# dashbutton_round_v2.net
KiCad netlist of a schematic drawn in EAGLE
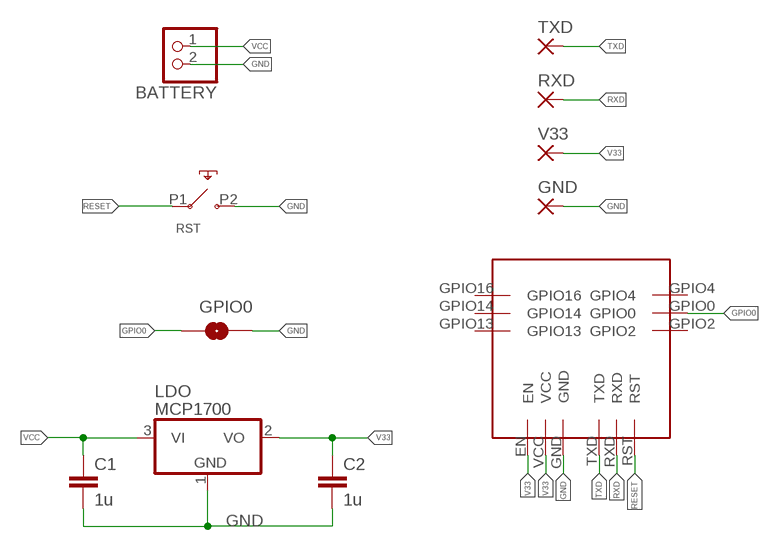
[diagram p0: schematic, sheet 1]

(export (version "E")
  (design (tool "Eeschema 10.0.6"))
  (components
    (comp (ref "BATTERY")
      (value "JST_2PIN-SMT-RA")
      (footprint "eagle-import:JST-PH-2-SMT-RA")
      (libsource (lib "eagle-import") (part "JST_2PIN-SMT-RA"))
    )
    (comp (ref "C1")
      (value "1u")
      (footprint "eagle-import:C1206")
      (libsource (lib "eagle-import") (part "C-EUC1206"))
    )
    (comp (ref "C2")
      (value "1u")
      (footprint "eagle-import:C1206")
      (libsource (lib "eagle-import") (part "C-EUC1206"))
    )
    (comp (ref "GND")
      (value "WIREPADSMD1,27-254")
      (footprint "eagle-import:SMD1,27-2,54")
      (libsource (lib "eagle-import") (part "WIREPADSMD1,27-254"))
    )
    (comp (ref "GPIO0")
      (value "JUMPER-SMT_2_NO_NO-SILK")
      (footprint "eagle-import:SMT-JUMPER_2_NO_NO-SILK")
      (libsource (lib "eagle-import") (part "JUMPER-SMT_2_NO_NO-SILK"))
    )
    (comp (ref "LDO")
      (value "MCP1700")
      (footprint "eagle-import:SOT23")
      (libsource (lib "eagle-import") (part "MCP1703CB"))
    )
    (comp (ref "RST")
      (value "6X3_SMD_BUTTON_HALF")
      (footprint "eagle-import:6X3BUTTON")
      (libsource (lib "eagle-import") (part "6X3_SMD_BUTTON_HALF"))
    )
    (comp (ref "RXD")
      (value "WIREPADSMD1,27-254")
      (footprint "eagle-import:SMD1,27-2,54")
      (libsource (lib "eagle-import") (part "WIREPADSMD1,27-254"))
    )
    (comp (ref "TXD")
      (value "WIREPADSMD1,27-254")
      (footprint "eagle-import:SMD1,27-2,54")
      (libsource (lib "eagle-import") (part "WIREPADSMD1,27-254"))
    )
    (comp (ref "U$1")
      (value "ESP8285-M3")
      (footprint "eagle-import:ESP8285")
      (libsource (lib "eagle-import") (part "ESP8285-M3"))
    )
    (comp (ref "V33")
      (value "WIREPADSMD1,27-254")
      (footprint "eagle-import:SMD1,27-2,54")
      (libsource (lib "eagle-import") (part "WIREPADSMD1,27-254"))
    )
  )
  (nets
    (net (code "1") (name "GND") (class "Default")
      (node (ref "BATTERY") (pin "2") (pinfunction "1_2") (pintype "passive"))
      (node (ref "C1") (pin "2") (pinfunction "2_2") (pintype "passive"))
      (node (ref "C2") (pin "2") (pinfunction "2_2") (pintype "passive"))
      (node (ref "GND") (pin "1") (pinfunction "P_1") (pintype "passive"))
      (node (ref "GPIO0") (pin "2") (pinfunction "2_2") (pintype "passive"))
      (node (ref "LDO") (pin "1") (pinfunction "GND_1") (pintype "passive"))
      (node (ref "RST") (pin "P2") (pinfunction "P2_P2") (pintype "bidirectional"))
      (node (ref "U$1") (pin "GND") (pinfunction "GND_GND") (pintype "bidirectional"))
    )
    (net (code "2") (name "GPIO0") (class "Default")
      (node (ref "GPIO0") (pin "1") (pinfunction "1_1") (pintype "passive"))
      (node (ref "U$1") (pin "GPIO0") (pinfunction "GPIO0_GPIO0") (pintype "bidirectional"))
    )
    (net (code "3") (name "RESET") (class "Default")
      (node (ref "RST") (pin "P1") (pinfunction "P1_P1") (pintype "bidirectional"))
      (node (ref "U$1") (pin "RST") (pinfunction "RST_RST") (pintype "bidirectional"))
    )
    (net (code "4") (name "RXD") (class "Default")
      (node (ref "RXD") (pin "1") (pinfunction "P_1") (pintype "passive"))
      (node (ref "U$1") (pin "RXD") (pinfunction "RXD_RXD") (pintype "bidirectional"))
    )
    (net (code "5") (name "TXD") (class "Default")
      (node (ref "TXD") (pin "1") (pinfunction "P_1") (pintype "passive"))
      (node (ref "U$1") (pin "TXD") (pinfunction "TXD_TXD") (pintype "bidirectional"))
    )
    (net (code "6") (name "V33") (class "Default")
      (node (ref "C2") (pin "1") (pinfunction "1_1") (pintype "passive"))
      (node (ref "LDO") (pin "2") (pinfunction "VO_2") (pintype "passive"))
      (node (ref "U$1") (pin "EN") (pinfunction "EN_EN") (pintype "bidirectional"))
      (node (ref "U$1") (pin "VCC") (pinfunction "VCC_VCC") (pintype "bidirectional"))
      (node (ref "V33") (pin "1") (pinfunction "P_1") (pintype "passive"))
    )
    (net (code "7") (name "VCC") (class "Default")
      (node (ref "BATTERY") (pin "1") (pinfunction "2_1") (pintype "passive"))
      (node (ref "C1") (pin "1") (pinfunction "1_1") (pintype "passive"))
      (node (ref "LDO") (pin "3") (pinfunction "VI_3") (pintype "input"))
    )
    (net (code "8") (name "unconnected-(U$1-PadGPIO2)") (class "Default")
      (node (ref "U$1") (pin "GPIO2") (pinfunction "GPIO2_GPIO2") (pintype "bidirectional"))
    )
    (net (code "9") (name "unconnected-(U$1-PadGPIO4)") (class "Default")
      (node (ref "U$1") (pin "GPIO4") (pinfunction "GPIO4_GPIO4") (pintype "bidirectional"))
    )
    (net (code "10") (name "unconnected-(U$1-PadGPIO13)") (class "Default")
      (node (ref "U$1") (pin "GPIO13") (pinfunction "GPIO13_GPIO13") (pintype "bidirectional"))
    )
    (net (code "11") (name "unconnected-(U$1-PadGPIO14)") (class "Default")
      (node (ref "U$1") (pin "GPIO14") (pinfunction "GPIO14_GPIO14") (pintype "bidirectional"))
    )
    (net (code "12") (name "unconnected-(U$1-PadGPIO16)") (class "Default")
      (node (ref "U$1") (pin "GPIO16") (pinfunction "GPIO16_GPIO16") (pintype "bidirectional"))
    )
  )
)
